# Arduino_with_Ribbon_7_segment_display.net
KiCad netlist of a schematic drawn in EAGLE
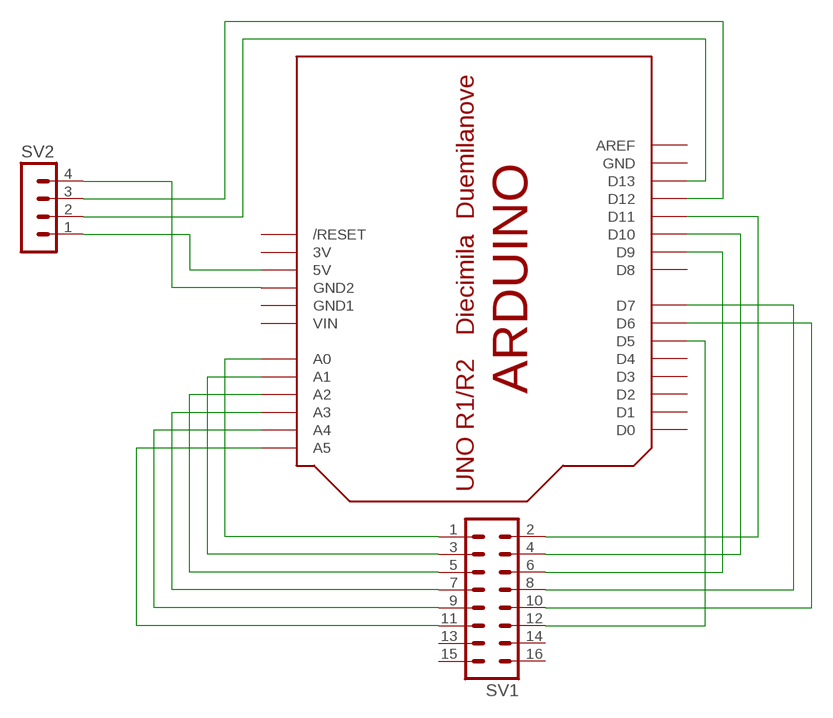
[diagram p0: schematic, sheet 1]

(export (version "E")
  (design (tool "Eeschema 10.0.6"))
  (components
    (comp (ref "SV1")
      (value "MA08-2")
      (footprint "eagle-import:MA08-2")
      (libsource (lib "eagle-import") (part "MA08-2"))
    )
    (comp (ref "SV2")
      (value "MA04-1")
      (footprint "eagle-import:MA04-1")
      (libsource (lib "eagle-import") (part "MA04-1"))
    )
    (comp (ref "U$1")
      (value "ARDUINO-BPLACE")
      (footprint "eagle-import:ARDUINO-BPLACE")
      (libsource (lib "eagle-import") (part "ARDUINO-BPLACE"))
    )
  )
  (nets
    (net (code "1") (name "/3V") (class "Default")
      (node (ref "U$1") (pin "3V") (pinfunction "3V_3V") (pintype "power_in"))
    )
    (net (code "2") (name "/GND") (class "Default")
      (node (ref "U$1") (pin "GND") (pinfunction "GND_GND") (pintype "power_in"))
    )
    (net (code "3") (name "/GND1") (class "Default")
      (node (ref "U$1") (pin "GND1") (pinfunction "GND1_GND1") (pintype "power_in"))
    )
    (net (code "4") (name "/VIN") (class "Default")
      (node (ref "U$1") (pin "VIN") (pinfunction "VIN_VIN") (pintype "power_in"))
    )
    (net (code "5") (name "Net-(SV1-Pad1)") (class "Default")
      (node (ref "SV1") (pin "1") (pinfunction "1_1") (pintype "passive"))
      (node (ref "U$1") (pin "A0") (pinfunction "A0_A0") (pintype "bidirectional"))
    )
    (net (code "6") (name "Net-(SV1-Pad2)") (class "Default")
      (node (ref "SV1") (pin "2") (pinfunction "2_2") (pintype "passive"))
      (node (ref "U$1") (pin "D11") (pinfunction "D11_D11") (pintype "bidirectional"))
    )
    (net (code "7") (name "Net-(SV1-Pad3)") (class "Default")
      (node (ref "SV1") (pin "3") (pinfunction "3_3") (pintype "passive"))
      (node (ref "U$1") (pin "A1") (pinfunction "A1_A1") (pintype "bidirectional"))
    )
    (net (code "8") (name "Net-(SV1-Pad4)") (class "Default")
      (node (ref "SV1") (pin "4") (pinfunction "4_4") (pintype "passive"))
      (node (ref "U$1") (pin "D10") (pinfunction "D10_D10") (pintype "bidirectional"))
    )
    (net (code "9") (name "Net-(SV1-Pad5)") (class "Default")
      (node (ref "SV1") (pin "5") (pinfunction "5_5") (pintype "passive"))
      (node (ref "U$1") (pin "A2") (pinfunction "A2_A2") (pintype "bidirectional"))
    )
    (net (code "10") (name "Net-(SV1-Pad6)") (class "Default")
      (node (ref "SV1") (pin "6") (pinfunction "6_6") (pintype "passive"))
      (node (ref "U$1") (pin "D9") (pinfunction "D9_D9") (pintype "bidirectional"))
    )
    (net (code "11") (name "Net-(SV1-Pad7)") (class "Default")
      (node (ref "SV1") (pin "7") (pinfunction "7_7") (pintype "passive"))
      (node (ref "U$1") (pin "A3") (pinfunction "A3_A3") (pintype "bidirectional"))
    )
    (net (code "12") (name "Net-(SV1-Pad8)") (class "Default")
      (node (ref "SV1") (pin "8") (pinfunction "8_8") (pintype "passive"))
      (node (ref "U$1") (pin "D7") (pinfunction "D7_D7") (pintype "bidirectional"))
    )
    (net (code "13") (name "Net-(SV1-Pad9)") (class "Default")
      (node (ref "SV1") (pin "9") (pinfunction "9_9") (pintype "passive"))
      (node (ref "U$1") (pin "A4") (pinfunction "A4_A4") (pintype "bidirectional"))
    )
    (net (code "14") (name "Net-(SV1-Pad10)") (class "Default")
      (node (ref "SV1") (pin "10") (pinfunction "10_10") (pintype "passive"))
      (node (ref "U$1") (pin "D6") (pinfunction "D6_D6") (pintype "bidirectional"))
    )
    (net (code "15") (name "Net-(SV1-Pad11)") (class "Default")
      (node (ref "SV1") (pin "11") (pinfunction "11_11") (pintype "passive"))
      (node (ref "U$1") (pin "A5") (pinfunction "A5_A5") (pintype "bidirectional"))
    )
    (net (code "16") (name "Net-(SV1-Pad12)") (class "Default")
      (node (ref "SV1") (pin "12") (pinfunction "12_12") (pintype "passive"))
      (node (ref "U$1") (pin "D5") (pinfunction "D5_D5") (pintype "bidirectional"))
    )
    (net (code "17") (name "Net-(SV2-Pad1)") (class "Default")
      (node (ref "SV2") (pin "1") (pinfunction "1_1") (pintype "passive"))
      (node (ref "U$1") (pin "5V") (pinfunction "5V_5V") (pintype "power_in"))
    )
    (net (code "18") (name "Net-(SV2-Pad2)") (class "Default")
      (node (ref "SV2") (pin "2") (pinfunction "2_2") (pintype "passive"))
      (node (ref "U$1") (pin "D13") (pinfunction "D13_D13") (pintype "bidirectional"))
    )
    (net (code "19") (name "Net-(SV2-Pad3)") (class "Default")
      (node (ref "SV2") (pin "3") (pinfunction "3_3") (pintype "passive"))
      (node (ref "U$1") (pin "D12") (pinfunction "D12_D12") (pintype "bidirectional"))
    )
    (net (code "20") (name "Net-(SV2-Pad4)") (class "Default")
      (node (ref "SV2") (pin "4") (pinfunction "4_4") (pintype "passive"))
      (node (ref "U$1") (pin "GND2") (pinfunction "GND2_GND2") (pintype "power_in"))
    )
    (net (code "21") (name "unconnected-(SV1-Pad13)") (class "Default")
      (node (ref "SV1") (pin "13") (pinfunction "13_13") (pintype "passive"))
    )
    (net (code "22") (name "unconnected-(SV1-Pad14)") (class "Default")
      (node (ref "SV1") (pin "14") (pinfunction "14_14") (pintype "passive"))
    )
    (net (code "23") (name "unconnected-(SV1-Pad15)") (class "Default")
      (node (ref "SV1") (pin "15") (pinfunction "15_15") (pintype "passive"))
    )
    (net (code "24") (name "unconnected-(SV1-Pad16)") (class "Default")
      (node (ref "SV1") (pin "16") (pinfunction "16_16") (pintype "passive"))
    )
    (net (code "25") (name "unconnected-(U$1-PadAREF)") (class "Default")
      (node (ref "U$1") (pin "AREF") (pinfunction "AREF_AREF") (pintype "bidirectional"))
    )
    (net (code "26") (name "unconnected-(U$1-PadD0)") (class "Default")
      (node (ref "U$1") (pin "D0") (pinfunction "D0_D0") (pintype "bidirectional"))
    )
    (net (code "27") (name "unconnected-(U$1-PadD1)") (class "Default")
      (node (ref "U$1") (pin "D1") (pinfunction "D1_D1") (pintype "bidirectional"))
    )
    (net (code "28") (name "unconnected-(U$1-PadD2)") (class "Default")
      (node (ref "U$1") (pin "D2") (pinfunction "D2_D2") (pintype "bidirectional"))
    )
    (net (code "29") (name "unconnected-(U$1-PadD3)") (class "Default")
      (node (ref "U$1") (pin "D3") (pinfunction "D3_D3") (pintype "bidirectional"))
    )
    (net (code "30") (name "unconnected-(U$1-PadD4)") (class "Default")
      (node (ref "U$1") (pin "D4") (pinfunction "D4_D4") (pintype "bidirectional"))
    )
    (net (code "31") (name "unconnected-(U$1-PadD8)") (class "Default")
      (node (ref "U$1") (pin "D8") (pinfunction "D8_D8") (pintype "bidirectional"))
    )
    (net (code "32") (name "unconnected-(U$1-{slash}RESET-PadRESET)") (class "Default")
      (node (ref "U$1") (pin "RESET") (pinfunction "/RESET_RESET") (pintype "bidirectional"))
    )
  )
)
